# DAC.net
KiCad netlist of a schematic drawn in Altium Designer
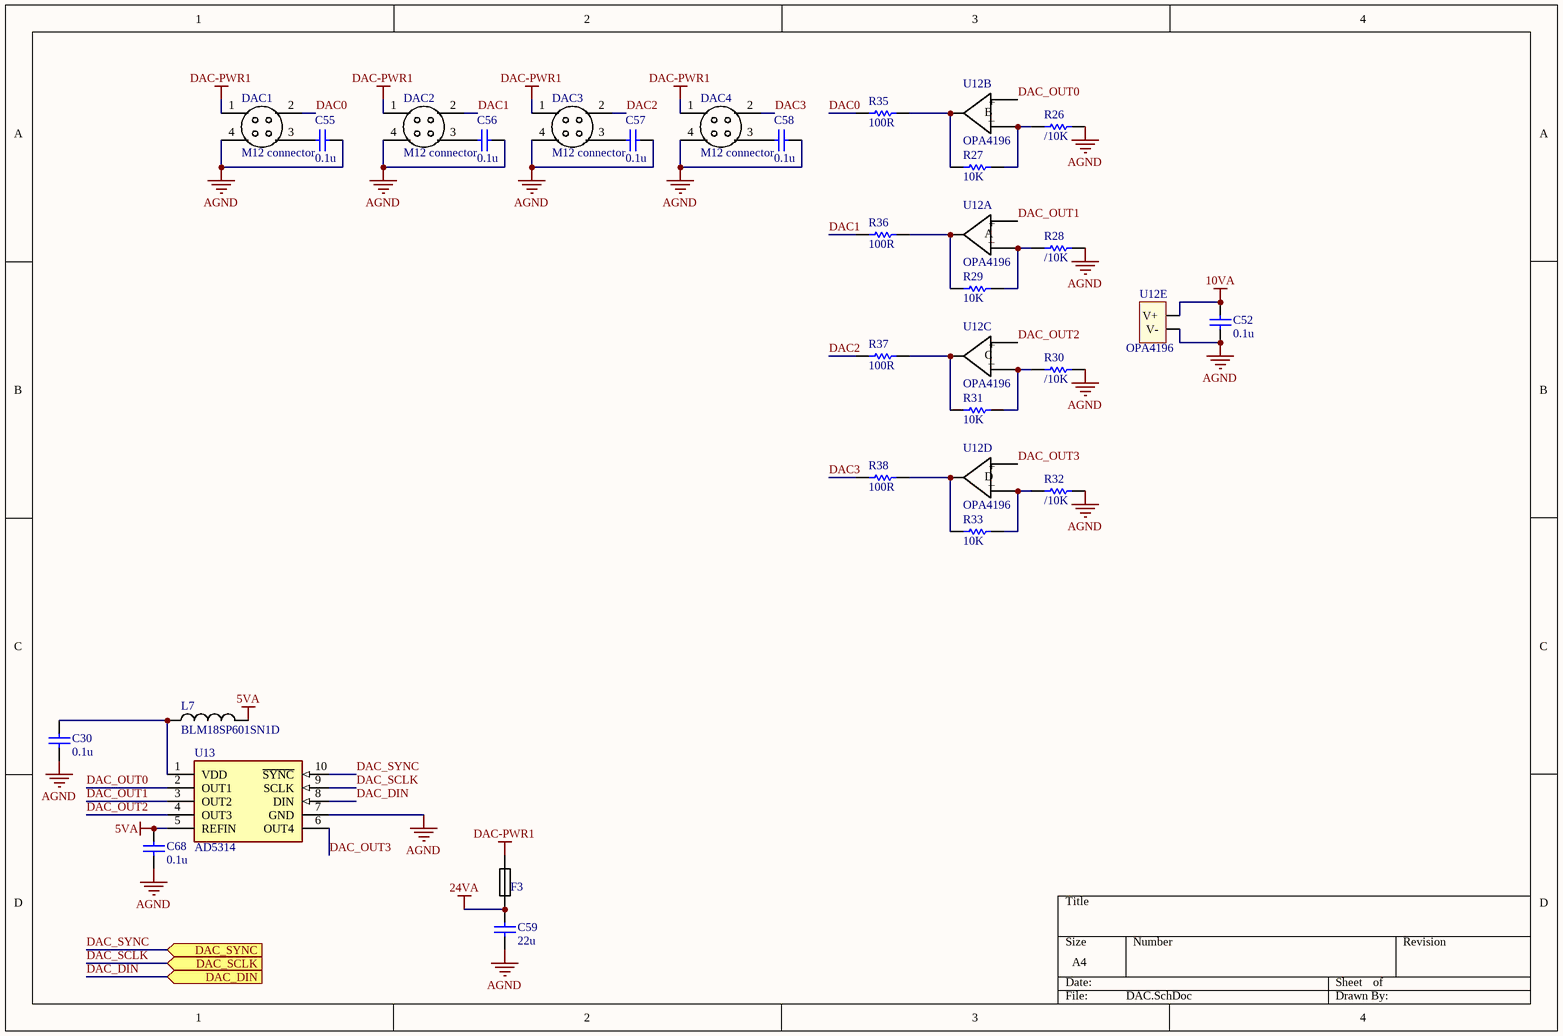
[diagram p0: DAC.SchDoc]

(export (version "E")
  (design (tool "Eeschema 10.0.6"))
  (components
    (comp (ref "C30")
      (value "0.1u")
      (footprint "CAPC1608X90N")
      (description "Capacitor")
      (fields (field (name "Comment") "Cap") (field (name "PUBLISHER") "Altium Limited"))
      (libsource (lib "IOBoard_Low") (part "Cap"))
    )
    (comp (ref "C52")
      (value "0.1u")
      (footprint "CAPC1608X90N")
      (description "Capacitor")
      (fields (field (name "Comment") "Cap") (field (name "PUBLISHER") "Altium Limited"))
      (libsource (lib "IOBoard_Low") (part "Cap"))
    )
    (comp (ref "C55")
      (value "0.1u")
      (footprint "CAPC1608X90N")
      (description "Capacitor")
      (fields (field (name "Comment") "Cap") (field (name "PUBLISHER") "Altium Limited"))
      (libsource (lib "IOBoard_Low") (part "Cap"))
    )
    (comp (ref "C56")
      (value "0.1u")
      (footprint "CAPC1608X90N")
      (description "Capacitor")
      (fields (field (name "Comment") "Cap") (field (name "PUBLISHER") "Altium Limited"))
      (libsource (lib "IOBoard_Low") (part "Cap"))
    )
    (comp (ref "C57")
      (value "0.1u")
      (footprint "CAPC1608X90N")
      (description "Capacitor")
      (fields (field (name "Comment") "Cap") (field (name "PUBLISHER") "Altium Limited"))
      (libsource (lib "IOBoard_Low") (part "Cap"))
    )
    (comp (ref "C58")
      (value "0.1u")
      (footprint "CAPC1608X90N")
      (description "Capacitor")
      (fields (field (name "Comment") "Cap") (field (name "PUBLISHER") "Altium Limited"))
      (libsource (lib "IOBoard_Low") (part "Cap"))
    )
    (comp (ref "C59")
      (value "22u")
      (footprint "CAPC2012X135N")
      (description "Capacitor")
      (fields (field (name "Comment") "Cap") (field (name "PUBLISHER") "Altium Limited"))
      (libsource (lib "IOBoard_Low") (part "Cap"))
    )
    (comp (ref "C68")
      (value "0.1u")
      (footprint "CAPC1608X90N")
      (description "Capacitor")
      (fields (field (name "Comment") "Cap") (field (name "PUBLISHER") "Altium Limited"))
      (libsource (lib "IOBoard_Low") (part "Cap"))
    )
    (comp (ref "DAC1")
      (value "M12 connector")
      (footprint "GX12_PCB_Mount")
      (description "M12 connect with 4 pin, current 4A per terminal")
      (libsource (lib "IOBoard") (part "M12_connector"))
    )
    (comp (ref "DAC2")
      (value "M12 connector")
      (footprint "GX12_PCB_Mount")
      (description "M12 connect with 4 pin, current 4A per terminal")
      (libsource (lib "IOBoard") (part "M12_connector"))
    )
    (comp (ref "DAC3")
      (value "M12 connector")
      (footprint "GX12_PCB_Mount")
      (description "M12 connect with 4 pin, current 4A per terminal")
      (libsource (lib "IOBoard") (part "M12_connector"))
    )
    (comp (ref "DAC4")
      (value "M12 connector")
      (footprint "GX12_PCB_Mount")
      (description "M12 connect with 4 pin, current 4A per terminal")
      (libsource (lib "IOBoard") (part "M12_connector"))
    )
    (comp (ref "F3")
      (value "MFU0805FF00500P100")
      (footprint "RESC2012X70N")
      (description "fuse 32V 0.5A")
      (libsource (lib "IOBoard") (part "FUSE_32V_500MA_0805"))
    )
    (comp (ref "L7")
      (value "BLM18SP601SN1D")
      (footprint "INDC1608N")
      (description "Ferritebead 1.5A, max 600ohm resistance")
      (libsource (lib "IOBoard") (part "INC_BLM18SP601SN1D"))
    )
    (comp (ref "R26")
      (value "/10K")
      (footprint "RESC1608X55N")
      (description "Resistor")
      (fields (field (name "Comment") "Res1") (field (name "PUBLISHER") "Altium Limited"))
      (libsource (lib "IOBoard") (part "Res1"))
    )
    (comp (ref "R27")
      (value "10K")
      (footprint "RESC1608X55N")
      (description "Resistor")
      (fields (field (name "Comment") "Res1") (field (name "PUBLISHER") "Altium Limited"))
      (libsource (lib "IOBoard") (part "Res1"))
    )
    (comp (ref "R28")
      (value "/10K")
      (footprint "RESC1608X55N")
      (description "Resistor")
      (fields (field (name "Comment") "Res1") (field (name "PUBLISHER") "Altium Limited"))
      (libsource (lib "IOBoard") (part "Res1"))
    )
    (comp (ref "R29")
      (value "10K")
      (footprint "RESC1608X55N")
      (description "Resistor")
      (fields (field (name "Comment") "Res1") (field (name "PUBLISHER") "Altium Limited"))
      (libsource (lib "IOBoard") (part "Res1"))
    )
    (comp (ref "R30")
      (value "/10K")
      (footprint "RESC1608X55N")
      (description "Resistor")
      (fields (field (name "Comment") "Res1") (field (name "PUBLISHER") "Altium Limited"))
      (libsource (lib "IOBoard") (part "Res1"))
    )
    (comp (ref "R31")
      (value "10K")
      (footprint "RESC1608X55N")
      (description "Resistor")
      (fields (field (name "Comment") "Res1") (field (name "PUBLISHER") "Altium Limited"))
      (libsource (lib "IOBoard") (part "Res1"))
    )
    (comp (ref "R32")
      (value "/10K")
      (footprint "RESC1608X55N")
      (description "Resistor")
      (fields (field (name "Comment") "Res1") (field (name "PUBLISHER") "Altium Limited"))
      (libsource (lib "IOBoard") (part "Res1"))
    )
    (comp (ref "R33")
      (value "10K")
      (footprint "RESC1608X55N")
      (description "Resistor")
      (fields (field (name "Comment") "Res1") (field (name "PUBLISHER") "Altium Limited"))
      (libsource (lib "IOBoard") (part "Res1"))
    )
    (comp (ref "R35")
      (value "100R")
      (footprint "RESC1608X55N")
      (description "Resistor")
      (fields (field (name "Comment") "Res1") (field (name "PUBLISHER") "Altium Limited"))
      (libsource (lib "IOBoard") (part "Res1"))
    )
    (comp (ref "R36")
      (value "100R")
      (footprint "RESC1608X55N")
      (description "Resistor")
      (fields (field (name "Comment") "Res1") (field (name "PUBLISHER") "Altium Limited"))
      (libsource (lib "IOBoard") (part "Res1"))
    )
    (comp (ref "R37")
      (value "100R")
      (footprint "RESC1608X55N")
      (description "Resistor")
      (fields (field (name "Comment") "Res1") (field (name "PUBLISHER") "Altium Limited"))
      (libsource (lib "IOBoard") (part "Res1"))
    )
    (comp (ref "R38")
      (value "100R")
      (footprint "RESC1608X55N")
      (description "Resistor")
      (fields (field (name "Comment") "Res1") (field (name "PUBLISHER") "Altium Limited"))
      (libsource (lib "IOBoard") (part "Res1"))
    )
    (comp (ref "U12")
      (value "OPA4196")
      (footprint "SOIC127P600X175-14AN")
      (description "operational amplifier 36V input")
      (libsource (lib "") (part "OPA4196_1"))
    )
    (comp (ref "U13")
      (value "AD5314")
      (footprint "MSOP10_no_EP")
      (description "10-bit DAC 4 channel")
      (libsource (lib "IOBoard") (part "AD5314"))
    )
  )
  (nets
    (net (code "1") (name "/DAC0") (class "Default")
      (node (ref "DAC1") (pin "2") (pinfunction "2_2") (pintype "power_in"))
      (node (ref "R35") (pin "1") (pinfunction "1_1") (pintype "passive"))
    )
    (net (code "2") (name "/DAC1") (class "Default")
      (node (ref "DAC2") (pin "2") (pinfunction "2_2") (pintype "power_in"))
      (node (ref "R36") (pin "1") (pinfunction "1_1") (pintype "passive"))
    )
    (net (code "3") (name "/DAC2") (class "Default")
      (node (ref "DAC3") (pin "2") (pinfunction "2_2") (pintype "power_in"))
      (node (ref "R37") (pin "1") (pinfunction "1_1") (pintype "passive"))
    )
    (net (code "4") (name "/DAC3") (class "Default")
      (node (ref "DAC4") (pin "2") (pinfunction "2_2") (pintype "power_in"))
      (node (ref "R38") (pin "1") (pinfunction "1_1") (pintype "passive"))
    )
    (net (code "5") (name "/DAC_DIN") (class "Default")
      (node (ref "U13") (pin "8") (pinfunction "DIN_8") (pintype "input"))
    )
    (net (code "6") (name "/DAC_OUT0") (class "Default")
      (node (ref "U12") (pin "5") (pinfunction "INB+_5") (pintype "passive"))
      (node (ref "U13") (pin "2") (pinfunction "OUT1_2") (pintype "passive"))
    )
    (net (code "7") (name "/DAC_OUT1") (class "Default")
      (node (ref "U12") (pin "3") (pinfunction "INA+_3") (pintype "passive"))
      (node (ref "U13") (pin "3") (pinfunction "OUT2_3") (pintype "passive"))
    )
    (net (code "8") (name "/DAC_OUT2") (class "Default")
      (node (ref "U12") (pin "10") (pinfunction "INC+_10") (pintype "passive"))
      (node (ref "U13") (pin "4") (pinfunction "OUT3_4") (pintype "passive"))
    )
    (net (code "9") (name "/DAC_OUT3") (class "Default")
      (node (ref "U12") (pin "12") (pinfunction "IND+_12") (pintype "passive"))
      (node (ref "U13") (pin "6") (pinfunction "OUT4_6") (pintype "passive"))
    )
    (net (code "10") (name "/DAC_SCLK") (class "Default")
      (node (ref "U13") (pin "9") (pinfunction "SCLK_9") (pintype "input"))
    )
    (net (code "11") (name "/DAC_SYNC") (class "Default")
      (node (ref "U13") (pin "10") (pinfunction "~{SYNC}_10") (pintype "input"))
    )
    (net (code "12") (name "5VA") (class "Default")
      (node (ref "C68") (pin "1") (pinfunction "1_1") (pintype "passive"))
      (node (ref "L7") (pin "1") (pinfunction "1_1") (pintype "passive"))
      (node (ref "U13") (pin "5") (pinfunction "REFIN_5") (pintype "passive"))
    )
    (net (code "13") (name "10VA") (class "Default")
      (node (ref "C52") (pin "1") (pinfunction "1_1") (pintype "passive"))
      (node (ref "U12") (pin "4") (pinfunction "V+_4") (pintype "power_in"))
    )
    (net (code "14") (name "24VA") (class "Default")
      (node (ref "C59") (pin "2") (pinfunction "2_2") (pintype "passive"))
      (node (ref "F3") (pin "1") (pintype "passive"))
    )
    (net (code "15") (name "AGND") (class "Default")
      (node (ref "C30") (pin "2") (pinfunction "2_2") (pintype "passive"))
      (node (ref "C52") (pin "2") (pinfunction "2_2") (pintype "passive"))
      (node (ref "C55") (pin "1") (pinfunction "1_1") (pintype "passive"))
      (node (ref "C56") (pin "1") (pinfunction "1_1") (pintype "passive"))
      (node (ref "C57") (pin "1") (pinfunction "1_1") (pintype "passive"))
      (node (ref "C58") (pin "1") (pinfunction "1_1") (pintype "passive"))
      (node (ref "C59") (pin "1") (pinfunction "1_1") (pintype "passive"))
      (node (ref "C68") (pin "2") (pinfunction "2_2") (pintype "passive"))
      (node (ref "DAC1") (pin "4") (pinfunction "4_4") (pintype "power_in"))
      (node (ref "DAC2") (pin "4") (pinfunction "4_4") (pintype "power_in"))
      (node (ref "DAC3") (pin "4") (pinfunction "4_4") (pintype "power_in"))
      (node (ref "DAC4") (pin "4") (pinfunction "4_4") (pintype "power_in"))
      (node (ref "R26") (pin "2") (pinfunction "2_2") (pintype "passive"))
      (node (ref "R28") (pin "2") (pinfunction "2_2") (pintype "passive"))
      (node (ref "R30") (pin "2") (pinfunction "2_2") (pintype "passive"))
      (node (ref "R32") (pin "2") (pinfunction "2_2") (pintype "passive"))
      (node (ref "U12") (pin "11") (pinfunction "V-_11") (pintype "power_in"))
      (node (ref "U13") (pin "7") (pinfunction "GND_7") (pintype "power_in"))
    )
    (net (code "16") (name "DAC-PWR1") (class "Default")
      (node (ref "DAC1") (pin "1") (pinfunction "1_1") (pintype "power_in"))
      (node (ref "DAC2") (pin "1") (pinfunction "1_1") (pintype "power_in"))
      (node (ref "DAC3") (pin "1") (pinfunction "1_1") (pintype "power_in"))
      (node (ref "DAC4") (pin "1") (pinfunction "1_1") (pintype "power_in"))
      (node (ref "F3") (pin "2") (pintype "passive"))
    )
    (net (code "17") (name "Net-(C55-Pad2)") (class "Default")
      (node (ref "C55") (pin "2") (pinfunction "2_2") (pintype "passive"))
      (node (ref "DAC1") (pin "3") (pinfunction "3_3") (pintype "power_in"))
    )
    (net (code "18") (name "Net-(C56-Pad2)") (class "Default")
      (node (ref "C56") (pin "2") (pinfunction "2_2") (pintype "passive"))
      (node (ref "DAC2") (pin "3") (pinfunction "3_3") (pintype "power_in"))
    )
    (net (code "19") (name "Net-(C57-Pad2)") (class "Default")
      (node (ref "C57") (pin "2") (pinfunction "2_2") (pintype "passive"))
      (node (ref "DAC3") (pin "3") (pinfunction "3_3") (pintype "power_in"))
    )
    (net (code "20") (name "Net-(C58-Pad2)") (class "Default")
      (node (ref "C58") (pin "2") (pinfunction "2_2") (pintype "passive"))
      (node (ref "DAC4") (pin "3") (pinfunction "3_3") (pintype "power_in"))
    )
    (net (code "21") (name "Net-(U12A-INA-)") (class "Default")
      (node (ref "R28") (pin "1") (pinfunction "1_1") (pintype "passive"))
      (node (ref "R29") (pin "2") (pinfunction "2_2") (pintype "passive"))
      (node (ref "U12") (pin "2") (pinfunction "INA-_2") (pintype "passive"))
    )
    (net (code "22") (name "Net-(U12A-OUT_A)") (class "Default")
      (node (ref "R29") (pin "1") (pinfunction "1_1") (pintype "passive"))
      (node (ref "R36") (pin "2") (pinfunction "2_2") (pintype "passive"))
      (node (ref "U12") (pin "1") (pinfunction "OUT_A_1") (pintype "passive"))
    )
    (net (code "23") (name "Net-(U12B-INB-)") (class "Default")
      (node (ref "R26") (pin "1") (pinfunction "1_1") (pintype "passive"))
      (node (ref "R27") (pin "2") (pinfunction "2_2") (pintype "passive"))
      (node (ref "U12") (pin "6") (pinfunction "INB-_6") (pintype "passive"))
    )
    (net (code "24") (name "Net-(U12B-OUT_B)") (class "Default")
      (node (ref "R27") (pin "1") (pinfunction "1_1") (pintype "passive"))
      (node (ref "R35") (pin "2") (pinfunction "2_2") (pintype "passive"))
      (node (ref "U12") (pin "7") (pinfunction "OUT_B_7") (pintype "passive"))
    )
    (net (code "25") (name "Net-(U12C-INC-)") (class "Default")
      (node (ref "R30") (pin "1") (pinfunction "1_1") (pintype "passive"))
      (node (ref "R31") (pin "2") (pinfunction "2_2") (pintype "passive"))
      (node (ref "U12") (pin "9") (pinfunction "INC-_9") (pintype "passive"))
    )
    (net (code "26") (name "Net-(U12C-OUT_C)") (class "Default")
      (node (ref "R31") (pin "1") (pinfunction "1_1") (pintype "passive"))
      (node (ref "R37") (pin "2") (pinfunction "2_2") (pintype "passive"))
      (node (ref "U12") (pin "8") (pinfunction "OUT_C_8") (pintype "passive"))
    )
    (net (code "27") (name "Net-(U12D-IND-)") (class "Default")
      (node (ref "R32") (pin "1") (pinfunction "1_1") (pintype "passive"))
      (node (ref "R33") (pin "2") (pinfunction "2_2") (pintype "passive"))
      (node (ref "U12") (pin "13") (pinfunction "IND-_13") (pintype "passive"))
    )
    (net (code "28") (name "Net-(U12D-OUT_D)") (class "Default")
      (node (ref "R33") (pin "1") (pinfunction "1_1") (pintype "passive"))
      (node (ref "R38") (pin "2") (pinfunction "2_2") (pintype "passive"))
      (node (ref "U12") (pin "14") (pinfunction "OUT_D_14") (pintype "passive"))
    )
    (net (code "29") (name "Net-(U13-VDD)") (class "Default")
      (node (ref "C30") (pin "1") (pinfunction "1_1") (pintype "passive"))
      (node (ref "L7") (pin "2") (pinfunction "2_2") (pintype "passive"))
      (node (ref "U13") (pin "1") (pinfunction "VDD_1") (pintype "power_in"))
    )
  )
)
